# ws2812_v2.net
KiCad netlist of a schematic drawn in EAGLE
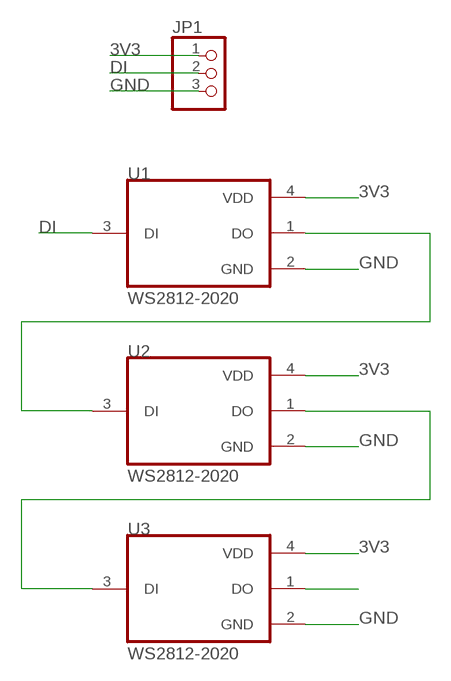
[diagram p0: schematic, sheet 1]

(export (version "E")
  (design (tool "Eeschema 10.0.6"))
  (components
    (comp (ref "JP1")
      (value "PINHD-1X3")
      (footprint "eagle-import:1X03")
      (libsource (lib "eagle-import") (part "PINHD-1X3"))
    )
    (comp (ref "U1")
      (value "WS2812-2020")
      (footprint "eagle-import:LED_WS2812-2020")
      (fields (field (name "MF") "Worldsemi"))
      (libsource (lib "eagle-import") (part "WS2812-2020"))
    )
    (comp (ref "U2")
      (value "WS2812-2020")
      (footprint "eagle-import:LED_WS2812-2020")
      (fields (field (name "MF") "Worldsemi"))
      (libsource (lib "eagle-import") (part "WS2812-2020"))
    )
    (comp (ref "U3")
      (value "WS2812-2020")
      (footprint "eagle-import:LED_WS2812-2020")
      (fields (field (name "MF") "Worldsemi"))
      (libsource (lib "eagle-import") (part "WS2812-2020"))
    )
  )
  (nets
    (net (code "1") (name "/3V3") (class "Default")
      (node (ref "JP1") (pin "1") (pinfunction "1_1") (pintype "passive"))
      (node (ref "U1") (pin "4") (pinfunction "VDD_4") (pintype "power_in"))
      (node (ref "U2") (pin "4") (pinfunction "VDD_4") (pintype "power_in"))
      (node (ref "U3") (pin "4") (pinfunction "VDD_4") (pintype "power_in"))
    )
    (net (code "2") (name "/DI") (class "Default")
      (node (ref "JP1") (pin "2") (pinfunction "2_2") (pintype "passive"))
      (node (ref "U1") (pin "3") (pinfunction "DI_3") (pintype "input"))
    )
    (net (code "3") (name "/GND") (class "Default")
      (node (ref "JP1") (pin "3") (pinfunction "3_3") (pintype "passive"))
      (node (ref "U1") (pin "2") (pinfunction "GND_2") (pintype "power_in"))
      (node (ref "U2") (pin "2") (pinfunction "GND_2") (pintype "power_in"))
      (node (ref "U3") (pin "2") (pinfunction "GND_2") (pintype "power_in"))
    )
    (net (code "4") (name "Net-(U1-DO)") (class "Default")
      (node (ref "U1") (pin "1") (pinfunction "DO_1") (pintype "output"))
      (node (ref "U2") (pin "3") (pinfunction "DI_3") (pintype "input"))
    )
    (net (code "5") (name "Net-(U2-DO)") (class "Default")
      (node (ref "U2") (pin "1") (pinfunction "DO_1") (pintype "output"))
      (node (ref "U3") (pin "3") (pinfunction "DI_3") (pintype "input"))
    )
    (net (code "6") (name "unconnected-(U3-DO-Pad1)") (class "Default")
      (node (ref "U3") (pin "1") (pinfunction "DO_1") (pintype "output"))
    )
  )
)
